# 3x_74HC595.net
KiCad netlist of a schematic drawn in EAGLE
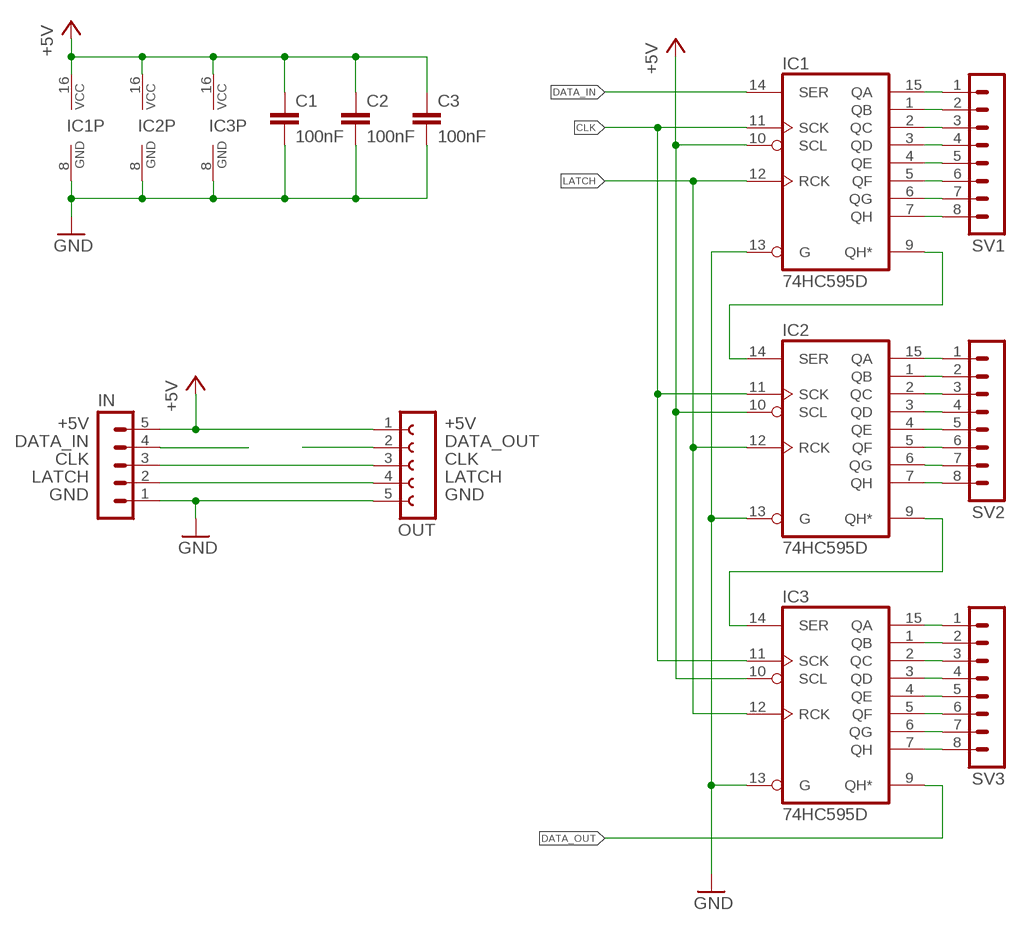
[diagram p0: schematic, sheet 1]

(export (version "E")
  (design (tool "Eeschema 10.0.6"))
  (components
    (comp (ref "C1")
      (value "100nF")
      (footprint "eagle-import:C1206")
      (libsource (lib "eagle-import") (part "C-EUC1206"))
    )
    (comp (ref "C2")
      (value "100nF")
      (footprint "eagle-import:C1206")
      (libsource (lib "eagle-import") (part "C-EUC1206"))
    )
    (comp (ref "C3")
      (value "100nF")
      (footprint "eagle-import:C1206")
      (libsource (lib "eagle-import") (part "C-EUC1206"))
    )
    (comp (ref "IC1")
      (value "74HC595D")
      (footprint "eagle-import:SO16")
      (libsource (lib "eagle-import") (part "74595DHC"))
    )
    (comp (ref "IC2")
      (value "74HC595D")
      (footprint "eagle-import:SO16")
      (libsource (lib "eagle-import") (part "74595DHC"))
    )
    (comp (ref "IC3")
      (value "74HC595D")
      (footprint "eagle-import:SO16")
      (libsource (lib "eagle-import") (part "74595DHC"))
    )
    (comp (ref "IN")
      (value "MA05-1W")
      (footprint "eagle-import:MA05-1W")
      (libsource (lib "eagle-import") (part "MA05-1W"))
    )
    (comp (ref "OUT")
      (value "FE05W")
      (footprint "eagle-import:FE05W")
      (libsource (lib "eagle-import") (part "FE05W"))
    )
    (comp (ref "SV1")
      (value "MA08-1W")
      (footprint "eagle-import:MA08-1W")
      (libsource (lib "eagle-import") (part "MA08-1W"))
    )
    (comp (ref "SV2")
      (value "MA08-1W")
      (footprint "eagle-import:MA08-1W")
      (libsource (lib "eagle-import") (part "MA08-1W"))
    )
    (comp (ref "SV3")
      (value "MA08-1W")
      (footprint "eagle-import:MA08-1W")
      (libsource (lib "eagle-import") (part "MA08-1W"))
    )
  )
  (nets
    (net (code "1") (name "+5V") (class "Default")
      (node (ref "C1") (pin "1") (pinfunction "1_1") (pintype "passive"))
      (node (ref "C2") (pin "1") (pinfunction "1_1") (pintype "passive"))
      (node (ref "C3") (pin "1") (pinfunction "1_1") (pintype "passive"))
      (node (ref "IC1") (pin "10") (pinfunction "SCL_10") (pintype "input"))
      (node (ref "IC1") (pin "16") (pinfunction "VCC_16") (pintype "power_in"))
      (node (ref "IC2") (pin "10") (pinfunction "SCL_10") (pintype "input"))
      (node (ref "IC2") (pin "16") (pinfunction "VCC_16") (pintype "power_in"))
      (node (ref "IC3") (pin "10") (pinfunction "SCL_10") (pintype "input"))
      (node (ref "IC3") (pin "16") (pinfunction "VCC_16") (pintype "power_in"))
      (node (ref "IN") (pin "5") (pinfunction "5_5") (pintype "passive"))
      (node (ref "OUT") (pin "1") (pinfunction "1_1") (pintype "passive"))
    )
    (net (code "2") (name "CLK") (class "Default")
      (node (ref "IC1") (pin "11") (pinfunction "SCK_11") (pintype "input"))
      (node (ref "IC2") (pin "11") (pinfunction "SCK_11") (pintype "input"))
      (node (ref "IC3") (pin "11") (pinfunction "SCK_11") (pintype "input"))
      (node (ref "IN") (pin "3") (pinfunction "3_3") (pintype "passive"))
      (node (ref "OUT") (pin "3") (pinfunction "3_3") (pintype "passive"))
    )
    (net (code "3") (name "DATA_IN") (class "Default")
      (node (ref "IC1") (pin "14") (pinfunction "SER_14") (pintype "input"))
      (node (ref "IN") (pin "4") (pinfunction "4_4") (pintype "passive"))
    )
    (net (code "4") (name "DATA_OUT") (class "Default")
      (node (ref "IC3") (pin "9") (pinfunction "QH*_9") (pintype "tri_state"))
      (node (ref "OUT") (pin "2") (pinfunction "2_2") (pintype "passive"))
    )
    (net (code "5") (name "GND") (class "Default")
      (node (ref "C1") (pin "2") (pinfunction "2_2") (pintype "passive"))
      (node (ref "C2") (pin "2") (pinfunction "2_2") (pintype "passive"))
      (node (ref "C3") (pin "2") (pinfunction "2_2") (pintype "passive"))
      (node (ref "IC1") (pin "13") (pinfunction "G_13") (pintype "input"))
      (node (ref "IC1") (pin "8") (pinfunction "GND_8") (pintype "power_in"))
      (node (ref "IC2") (pin "13") (pinfunction "G_13") (pintype "input"))
      (node (ref "IC2") (pin "8") (pinfunction "GND_8") (pintype "power_in"))
      (node (ref "IC3") (pin "13") (pinfunction "G_13") (pintype "input"))
      (node (ref "IC3") (pin "8") (pinfunction "GND_8") (pintype "power_in"))
      (node (ref "IN") (pin "1") (pinfunction "1_1") (pintype "passive"))
      (node (ref "OUT") (pin "5") (pinfunction "5_5") (pintype "passive"))
    )
    (net (code "6") (name "LATCH") (class "Default")
      (node (ref "IC1") (pin "12") (pinfunction "RCK_12") (pintype "input"))
      (node (ref "IC2") (pin "12") (pinfunction "RCK_12") (pintype "input"))
      (node (ref "IC3") (pin "12") (pinfunction "RCK_12") (pintype "input"))
      (node (ref "IN") (pin "2") (pinfunction "2_2") (pintype "passive"))
      (node (ref "OUT") (pin "4") (pinfunction "4_4") (pintype "passive"))
    )
    (net (code "7") (name "Net-(IC1A-QA)") (class "Default")
      (node (ref "IC1") (pin "15") (pinfunction "QA_15") (pintype "tri_state"))
      (node (ref "SV1") (pin "1") (pinfunction "1_1") (pintype "passive"))
    )
    (net (code "8") (name "Net-(IC1A-QB)") (class "Default")
      (node (ref "IC1") (pin "1") (pinfunction "QB_1") (pintype "tri_state"))
      (node (ref "SV1") (pin "2") (pinfunction "2_2") (pintype "passive"))
    )
    (net (code "9") (name "Net-(IC1A-QC)") (class "Default")
      (node (ref "IC1") (pin "2") (pinfunction "QC_2") (pintype "tri_state"))
      (node (ref "SV1") (pin "3") (pinfunction "3_3") (pintype "passive"))
    )
    (net (code "10") (name "Net-(IC1A-QD)") (class "Default")
      (node (ref "IC1") (pin "3") (pinfunction "QD_3") (pintype "tri_state"))
      (node (ref "SV1") (pin "4") (pinfunction "4_4") (pintype "passive"))
    )
    (net (code "11") (name "Net-(IC1A-QE)") (class "Default")
      (node (ref "IC1") (pin "4") (pinfunction "QE_4") (pintype "tri_state"))
      (node (ref "SV1") (pin "5") (pinfunction "5_5") (pintype "passive"))
    )
    (net (code "12") (name "Net-(IC1A-QF)") (class "Default")
      (node (ref "IC1") (pin "5") (pinfunction "QF_5") (pintype "tri_state"))
      (node (ref "SV1") (pin "6") (pinfunction "6_6") (pintype "passive"))
    )
    (net (code "13") (name "Net-(IC1A-QG)") (class "Default")
      (node (ref "IC1") (pin "6") (pinfunction "QG_6") (pintype "tri_state"))
      (node (ref "SV1") (pin "7") (pinfunction "7_7") (pintype "passive"))
    )
    (net (code "14") (name "Net-(IC1A-QH)") (class "Default")
      (node (ref "IC1") (pin "7") (pinfunction "QH_7") (pintype "tri_state"))
      (node (ref "SV1") (pin "8") (pinfunction "8_8") (pintype "passive"))
    )
    (net (code "15") (name "Net-(IC1A-QH*)") (class "Default")
      (node (ref "IC1") (pin "9") (pinfunction "QH*_9") (pintype "tri_state"))
      (node (ref "IC2") (pin "14") (pinfunction "SER_14") (pintype "input"))
    )
    (net (code "16") (name "Net-(IC2A-QA)") (class "Default")
      (node (ref "IC2") (pin "15") (pinfunction "QA_15") (pintype "tri_state"))
      (node (ref "SV2") (pin "1") (pinfunction "1_1") (pintype "passive"))
    )
    (net (code "17") (name "Net-(IC2A-QB)") (class "Default")
      (node (ref "IC2") (pin "1") (pinfunction "QB_1") (pintype "tri_state"))
      (node (ref "SV2") (pin "2") (pinfunction "2_2") (pintype "passive"))
    )
    (net (code "18") (name "Net-(IC2A-QC)") (class "Default")
      (node (ref "IC2") (pin "2") (pinfunction "QC_2") (pintype "tri_state"))
      (node (ref "SV2") (pin "3") (pinfunction "3_3") (pintype "passive"))
    )
    (net (code "19") (name "Net-(IC2A-QD)") (class "Default")
      (node (ref "IC2") (pin "3") (pinfunction "QD_3") (pintype "tri_state"))
      (node (ref "SV2") (pin "4") (pinfunction "4_4") (pintype "passive"))
    )
    (net (code "20") (name "Net-(IC2A-QE)") (class "Default")
      (node (ref "IC2") (pin "4") (pinfunction "QE_4") (pintype "tri_state"))
      (node (ref "SV2") (pin "5") (pinfunction "5_5") (pintype "passive"))
    )
    (net (code "21") (name "Net-(IC2A-QF)") (class "Default")
      (node (ref "IC2") (pin "5") (pinfunction "QF_5") (pintype "tri_state"))
      (node (ref "SV2") (pin "6") (pinfunction "6_6") (pintype "passive"))
    )
    (net (code "22") (name "Net-(IC2A-QG)") (class "Default")
      (node (ref "IC2") (pin "6") (pinfunction "QG_6") (pintype "tri_state"))
      (node (ref "SV2") (pin "7") (pinfunction "7_7") (pintype "passive"))
    )
    (net (code "23") (name "Net-(IC2A-QH)") (class "Default")
      (node (ref "IC2") (pin "7") (pinfunction "QH_7") (pintype "tri_state"))
      (node (ref "SV2") (pin "8") (pinfunction "8_8") (pintype "passive"))
    )
    (net (code "24") (name "Net-(IC2A-QH*)") (class "Default")
      (node (ref "IC2") (pin "9") (pinfunction "QH*_9") (pintype "tri_state"))
      (node (ref "IC3") (pin "14") (pinfunction "SER_14") (pintype "input"))
    )
    (net (code "25") (name "Net-(IC3A-QA)") (class "Default")
      (node (ref "IC3") (pin "15") (pinfunction "QA_15") (pintype "tri_state"))
      (node (ref "SV3") (pin "1") (pinfunction "1_1") (pintype "passive"))
    )
    (net (code "26") (name "Net-(IC3A-QB)") (class "Default")
      (node (ref "IC3") (pin "1") (pinfunction "QB_1") (pintype "tri_state"))
      (node (ref "SV3") (pin "2") (pinfunction "2_2") (pintype "passive"))
    )
    (net (code "27") (name "Net-(IC3A-QC)") (class "Default")
      (node (ref "IC3") (pin "2") (pinfunction "QC_2") (pintype "tri_state"))
      (node (ref "SV3") (pin "3") (pinfunction "3_3") (pintype "passive"))
    )
    (net (code "28") (name "Net-(IC3A-QD)") (class "Default")
      (node (ref "IC3") (pin "3") (pinfunction "QD_3") (pintype "tri_state"))
      (node (ref "SV3") (pin "4") (pinfunction "4_4") (pintype "passive"))
    )
    (net (code "29") (name "Net-(IC3A-QE)") (class "Default")
      (node (ref "IC3") (pin "4") (pinfunction "QE_4") (pintype "tri_state"))
      (node (ref "SV3") (pin "5") (pinfunction "5_5") (pintype "passive"))
    )
    (net (code "30") (name "Net-(IC3A-QF)") (class "Default")
      (node (ref "IC3") (pin "5") (pinfunction "QF_5") (pintype "tri_state"))
      (node (ref "SV3") (pin "6") (pinfunction "6_6") (pintype "passive"))
    )
    (net (code "31") (name "Net-(IC3A-QG)") (class "Default")
      (node (ref "IC3") (pin "6") (pinfunction "QG_6") (pintype "tri_state"))
      (node (ref "SV3") (pin "7") (pinfunction "7_7") (pintype "passive"))
    )
    (net (code "32") (name "Net-(IC3A-QH)") (class "Default")
      (node (ref "IC3") (pin "7") (pinfunction "QH_7") (pintype "tri_state"))
      (node (ref "SV3") (pin "8") (pinfunction "8_8") (pintype "passive"))
    )
  )
)
